# Sheet1_1.net
KiCad netlist of a schematic drawn in Altium Designer
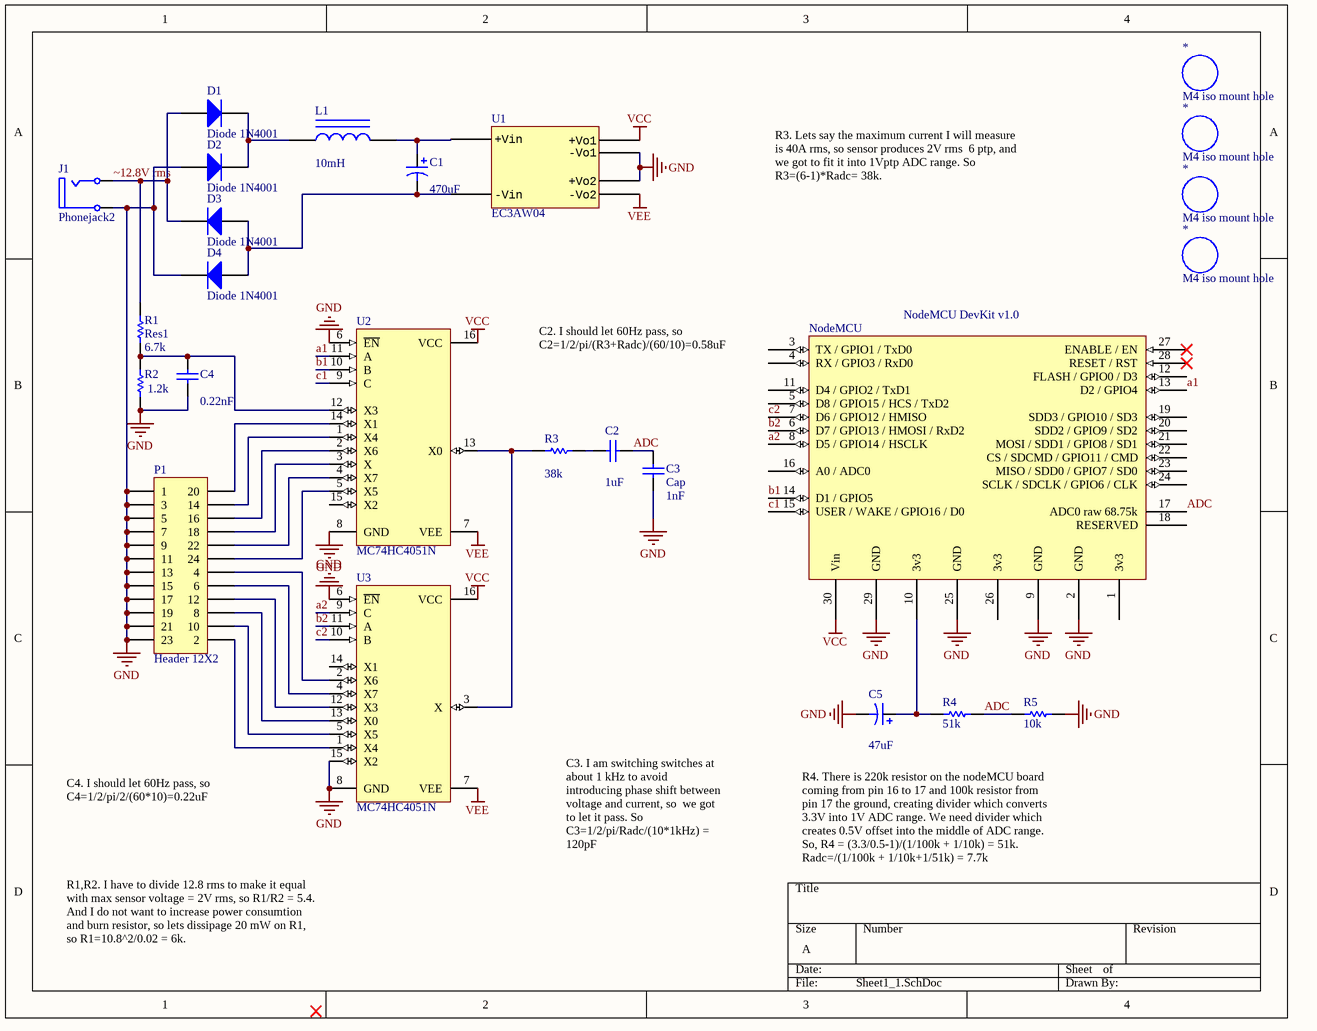
[diagram p0: Sheet1_1.SchDoc]

(export (version "E")
  (design (tool "Eeschema 10.0.6"))
  (components
    (comp (ref "C1")
      (value "470uF")
      (footprint "CAPPR5-12.5x25")
      (description "Polarized Capacitor (Radial)")
      (fields (field (name "Comment") "Cap Pol1") (field (name "PUBLISHER") "Altium Limited"))
      (libsource (lib "Miscellaneous Devices") (part "Cap Pol1"))
    )
    (comp (ref "C2")
      (value "1uF")
      (footprint "RAD-0.3")
      (description "Capacitor")
      (fields (field (name "Comment") "Cap") (field (name "PUBLISHER") "Altium Limited"))
      (libsource (lib "Miscellaneous Devices") (part "Cap"))
    )
    (comp (ref "C3")
      (value "Cap")
      (footprint "RAD-0.3")
      (description "Capacitor")
      (fields (field (name "ALTIUM_VALUE") "1nF") (field (name "PUBLISHER") "Altium Limited"))
      (libsource (lib "Miscellaneous Devices") (part "Cap"))
    )
    (comp (ref "C4")
      (value "0.22nF")
      (footprint "RAD-0.3")
      (description "Capacitor")
      (fields (field (name "Comment") "Cap") (field (name "PUBLISHER") "Altium Limited"))
      (libsource (lib "Miscellaneous Devices") (part "Cap"))
    )
    (comp (ref "C5")
      (value "47uF")
      (footprint "CAPPR2.5-6.3x6.8/H.9")
      (description "Polarized Capacitor (Radial)")
      (fields (field (name "Comment") "Cap Pol1") (field (name "PUBLISHER") "Altium Limited"))
      (libsource (lib "Miscellaneous Devices") (part "Cap Pol1"))
    )
    (comp (ref "D1")
      (value "Diode 1N4001")
      (footprint "DO-41")
      (description "1 Amp General Purpose Rectifier")
      (fields (field (name "PUBLISHER") "Altium Limited"))
      (libsource (lib "Miscellaneous Devices") (part "Diode 1N4001"))
    )
    (comp (ref "D2")
      (value "Diode 1N4001")
      (footprint "DO-41")
      (description "1 Amp General Purpose Rectifier")
      (fields (field (name "PUBLISHER") "Altium Limited"))
      (libsource (lib "Miscellaneous Devices") (part "Diode 1N4001"))
    )
    (comp (ref "D3")
      (value "Diode 1N4001")
      (footprint "DO-41")
      (description "1 Amp General Purpose Rectifier")
      (fields (field (name "PUBLISHER") "Altium Limited"))
      (libsource (lib "Miscellaneous Devices") (part "Diode 1N4001"))
    )
    (comp (ref "D4")
      (value "Diode 1N4001")
      (footprint "DO-41")
      (description "1 Amp General Purpose Rectifier")
      (fields (field (name "PUBLISHER") "Altium Limited"))
      (libsource (lib "Miscellaneous Devices") (part "Diode 1N4001"))
    )
    (comp (ref "J1")
      (value "Phonejack2")
      (footprint "Power jack 6x2mm")
      (description "Jack Socket, 1/4\" [6.5mm], Thru-Hole, Vertical, 2-Conductor Open Circuit")
      (fields (field (name "PUBLISHER") "Altium Limited"))
      (libsource (lib "AVP") (part "Phonejack2"))
    )
    (comp (ref "L1")
      (value "10mH")
      (footprint "Radial Vert Cylinder 10x19-6mm")
      (description "Magnetic-Core Inductor")
      (fields (field (name "Comment") "Inductor Iron") (field (name "PUBLISHER") "Altium Limited"))
      (libsource (lib "Miscellaneous Devices") (part "Inductor Iron"))
    )
    (comp (ref "NodeMCU")
      (value "NodeMCU DevKit v1.0")
      (footprint "NodeMCU DevKit v1.0 - Inside Labels")
      (libsource (lib "NodeMCU") (part "NodeMCU DevKit v1.0"))
    )
    (comp (ref "P1")
      (value "Header 12X2")
      (footprint "HDR2X12")
      (description "Header, 12-Pin, Dual row")
      (fields (field (name "PUBLISHER") "Altium Limited"))
      (libsource (lib "Miscellaneous Connectors") (part "Header 12X2"))
    )
    (comp (ref "R1")
      (value "Res1")
      (footprint "AXIAL-0.3")
      (description "Resistor")
      (fields (field (name "ALTIUM_VALUE") "6.7k") (field (name "PUBLISHER") "Altium Limited"))
      (libsource (lib "Miscellaneous Devices") (part "Res1"))
    )
    (comp (ref "R2")
      (value "1.2k")
      (footprint "AXIAL-0.3")
      (description "Resistor")
      (fields (field (name "Comment") "Res1") (field (name "PUBLISHER") "Altium Limited"))
      (libsource (lib "Miscellaneous Devices") (part "Res1"))
    )
    (comp (ref "R3")
      (value "38k")
      (footprint "AXIAL-0.3")
      (description "Resistor")
      (fields (field (name "Comment") "Res1") (field (name "PUBLISHER") "Altium Limited"))
      (libsource (lib "Miscellaneous Devices") (part "Res1"))
    )
    (comp (ref "R4")
      (value "51k")
      (footprint "AXIAL-0.3")
      (description "Resistor")
      (fields (field (name "Comment") "Res1") (field (name "PUBLISHER") "Altium Limited"))
      (libsource (lib "Miscellaneous Devices") (part "Res1"))
    )
    (comp (ref "R5")
      (value "10k")
      (footprint "AXIAL-0.3")
      (description "Resistor")
      (fields (field (name "Comment") "Res1") (field (name "PUBLISHER") "Altium Limited"))
      (libsource (lib "Miscellaneous Devices") (part "Res1"))
    )
    (comp (ref "U1") (value "EC3AW04") (footprint "EC3AW") (libsource (lib "AVP") (part "EC3AW04")))
    (comp (ref "U2")
      (value "MC74HC4051N")
      (footprint "648-08")
      (description "8-Channel Analog Multiplexer/Demultiplexer")
      (fields (field (name "PUBLISHER") "Altium Limited"))
      (libsource (lib "") (part "MC74HC4051N_1"))
    )
    (comp (ref "U3")
      (value "MC74HC4051N")
      (footprint "648-08")
      (description "8-Channel Analog Multiplexer/Demultiplexer")
      (fields (field (name "PUBLISHER") "Altium Limited"))
      (libsource (lib "ON Semi Logic Multiplexer") (part "MC74HC4051N"))
    )
  )
  (nets
    (net (code "1") (name "/ADC") (class "Default")
      (node (ref "C2") (pin "1") (pinfunction "1_1") (pintype "passive"))
      (node (ref "C3") (pin "2") (pinfunction "2_2") (pintype "passive"))
      (node (ref "NodeMCU") (pin "17") (pinfunction "ADC0_raw_68.75k_17") (pintype "passive"))
      (node (ref "R4") (pin "1") (pinfunction "1_1") (pintype "passive"))
      (node (ref "R5") (pin "2") (pinfunction "2_2") (pintype "passive"))
    )
    (net (code "2") (name "/a1") (class "Default")
      (node (ref "NodeMCU") (pin "13") (pinfunction "D2_/_GPIO4_13") (pintype "bidirectional"))
      (node (ref "U2") (pin "11") (pinfunction "A_11") (pintype "input"))
    )
    (net (code "3") (name "/a2") (class "Default")
      (node (ref "NodeMCU") (pin "8") (pinfunction "D5_/_GPIO14_/_HSCLK_8") (pintype "bidirectional"))
      (node (ref "U3") (pin "9") (pinfunction "C_9") (pintype "input"))
    )
    (net (code "4") (name "/b1") (class "Default")
      (node (ref "NodeMCU") (pin "14") (pinfunction "D1_/_GPIO5_14") (pintype "bidirectional"))
      (node (ref "U2") (pin "10") (pinfunction "B_10") (pintype "input"))
    )
    (net (code "5") (name "/b2") (class "Default")
      (node (ref "NodeMCU") (pin "6") (pinfunction "D7_/_GPIO13_/_HMOSI_/_RxD2_6") (pintype "bidirectional"))
      (node (ref "U3") (pin "11") (pinfunction "A_11") (pintype "input"))
    )
    (net (code "6") (name "/c1") (class "Default")
      (node (ref "NodeMCU") (pin "15") (pinfunction "USER_/_WAKE_/_GPIO16_/_D0_15") (pintype "bidirectional"))
      (node (ref "U2") (pin "9") (pinfunction "C_9") (pintype "input"))
    )
    (net (code "7") (name "/c2") (class "Default")
      (node (ref "NodeMCU") (pin "7") (pinfunction "D6_/_GPIO12_/_HMISO_7") (pintype "bidirectional"))
      (node (ref "U3") (pin "10") (pinfunction "B_10") (pintype "input"))
    )
    (net (code "8") (name "/~12.8V rms") (class "Default")
      (node (ref "D1") (pin "1") (pinfunction "A_1") (pintype "passive"))
      (node (ref "D3") (pin "2") (pinfunction "K_2") (pintype "passive"))
      (node (ref "J1") (pin "1") (pinfunction "T_1") (pintype "passive"))
      (node (ref "R1") (pin "2") (pinfunction "2_2") (pintype "passive"))
    )
    (net (code "9") (name "GND") (class "Default")
      (node (ref "C3") (pin "1") (pinfunction "1_1") (pintype "passive"))
      (node (ref "C4") (pin "1") (pinfunction "1_1") (pintype "passive"))
      (node (ref "C5") (pin "2") (pinfunction "2_2") (pintype "passive"))
      (node (ref "D2") (pin "1") (pinfunction "A_1") (pintype "passive"))
      (node (ref "D4") (pin "2") (pinfunction "K_2") (pintype "passive"))
      (node (ref "J1") (pin "5") (pinfunction "S_5") (pintype "power_in"))
      (node (ref "NodeMCU") (pin "2") (pinfunction "GND_2") (pintype "power_in"))
      (node (ref "NodeMCU") (pin "25") (pinfunction "GND_25") (pintype "power_in"))
      (node (ref "NodeMCU") (pin "29") (pinfunction "GND_29") (pintype "passive"))
      (node (ref "NodeMCU") (pin "9") (pinfunction "GND_9") (pintype "power_in"))
      (node (ref "P1") (pin "1") (pinfunction "1_1") (pintype "passive"))
      (node (ref "P1") (pin "11") (pinfunction "11_11") (pintype "passive"))
      (node (ref "P1") (pin "13") (pinfunction "13_13") (pintype "passive"))
      (node (ref "P1") (pin "15") (pinfunction "15_15") (pintype "passive"))
      (node (ref "P1") (pin "17") (pinfunction "17_17") (pintype "passive"))
      (node (ref "P1") (pin "19") (pinfunction "19_19") (pintype "passive"))
      (node (ref "P1") (pin "21") (pinfunction "21_21") (pintype "passive"))
      (node (ref "P1") (pin "23") (pinfunction "23_23") (pintype "passive"))
      (node (ref "P1") (pin "3") (pinfunction "3_3") (pintype "passive"))
      (node (ref "P1") (pin "5") (pinfunction "5_5") (pintype "passive"))
      (node (ref "P1") (pin "7") (pinfunction "7_7") (pintype "passive"))
      (node (ref "P1") (pin "9") (pinfunction "9_9") (pintype "passive"))
      (node (ref "R2") (pin "2") (pinfunction "2_2") (pintype "passive"))
      (node (ref "R5") (pin "1") (pinfunction "1_1") (pintype "passive"))
      (node (ref "U1") (pin "10") (pinfunction "-Vo1_10") (pintype "power_in"))
      (node (ref "U1") (pin "3") (pinfunction "+Vo2_3") (pintype "power_in"))
      (node (ref "U2") (pin "6") (pinfunction "~{EN}_6") (pintype "input"))
      (node (ref "U2") (pin "8") (pinfunction "GND_8") (pintype "power_in"))
      (node (ref "U3") (pin "15") (pinfunction "X2_15") (pintype "bidirectional"))
      (node (ref "U3") (pin "6") (pinfunction "~{EN}_6") (pintype "input"))
      (node (ref "U3") (pin "8") (pinfunction "GND_8") (pintype "power_in"))
    )
    (net (code "10") (name "Net-(C2-Pad2)") (class "Default")
      (node (ref "C2") (pin "2") (pinfunction "2_2") (pintype "passive"))
      (node (ref "R3") (pin "2") (pinfunction "2_2") (pintype "passive"))
    )
    (net (code "11") (name "Net-(C5-Pad1)") (class "Default")
      (node (ref "C5") (pin "1") (pinfunction "1_1") (pintype "passive"))
      (node (ref "NodeMCU") (pin "10") (pinfunction "3v3_10") (pintype "power_in"))
      (node (ref "R4") (pin "2") (pinfunction "2_2") (pintype "passive"))
    )
    (net (code "12") (name "Net-(D1-K)") (class "Default")
      (node (ref "D1") (pin "2") (pinfunction "K_2") (pintype "passive"))
      (node (ref "D2") (pin "2") (pinfunction "K_2") (pintype "passive"))
      (node (ref "L1") (pin "1") (pinfunction "1_1") (pintype "passive"))
    )
    (net (code "13") (name "Net-(D3-A)") (class "Default")
      (node (ref "C1") (pin "2") (pinfunction "2_2") (pintype "passive"))
      (node (ref "D3") (pin "1") (pinfunction "A_1") (pintype "passive"))
      (node (ref "D4") (pin "1") (pinfunction "A_1") (pintype "passive"))
      (node (ref "U1") (pin "12") (pinfunction "-Vin_12") (pintype "power_in"))
    )
    (net (code "14") (name "Net-(U1-+Vin)") (class "Default")
      (node (ref "C1") (pin "1") (pinfunction "1_1") (pintype "passive"))
      (node (ref "L1") (pin "2") (pinfunction "2_2") (pintype "passive"))
      (node (ref "U1") (pin "1") (pinfunction "+Vin_1") (pintype "power_in"))
    )
    (net (code "15") (name "Net-(U2-X)") (class "Default")
      (node (ref "P1") (pin "18") (pinfunction "18_18") (pintype "passive"))
      (node (ref "U2") (pin "3") (pinfunction "X_3") (pintype "bidirectional"))
    )
    (net (code "16") (name "Net-(U2-X0)") (class "Default")
      (node (ref "R3") (pin "1") (pinfunction "1_1") (pintype "passive"))
      (node (ref "U2") (pin "13") (pinfunction "X0_13") (pintype "bidirectional"))
      (node (ref "U3") (pin "3") (pinfunction "X_3") (pintype "bidirectional"))
    )
    (net (code "17") (name "Net-(U2-X1)") (class "Default")
      (node (ref "P1") (pin "20") (pinfunction "20_20") (pintype "passive"))
      (node (ref "U2") (pin "14") (pinfunction "X1_14") (pintype "bidirectional"))
    )
    (net (code "18") (name "Net-(U2-X3)") (class "Default")
      (node (ref "C4") (pin "2") (pinfunction "2_2") (pintype "passive"))
      (node (ref "R1") (pin "1") (pinfunction "1_1") (pintype "passive"))
      (node (ref "R2") (pin "1") (pinfunction "1_1") (pintype "passive"))
      (node (ref "U2") (pin "12") (pinfunction "X3_12") (pintype "bidirectional"))
    )
    (net (code "19") (name "Net-(U2-X4)") (class "Default")
      (node (ref "P1") (pin "14") (pinfunction "14_14") (pintype "passive"))
      (node (ref "U2") (pin "1") (pinfunction "X4_1") (pintype "bidirectional"))
    )
    (net (code "20") (name "Net-(U2-X5)") (class "Default")
      (node (ref "P1") (pin "24") (pinfunction "24_24") (pintype "passive"))
      (node (ref "U2") (pin "5") (pinfunction "X5_5") (pintype "bidirectional"))
    )
    (net (code "21") (name "Net-(U2-X6)") (class "Default")
      (node (ref "P1") (pin "16") (pinfunction "16_16") (pintype "passive"))
      (node (ref "U2") (pin "2") (pinfunction "X6_2") (pintype "bidirectional"))
    )
    (net (code "22") (name "Net-(U2-X7)") (class "Default")
      (node (ref "P1") (pin "22") (pinfunction "22_22") (pintype "passive"))
      (node (ref "U2") (pin "4") (pinfunction "X7_4") (pintype "bidirectional"))
    )
    (net (code "23") (name "Net-(U3-X0)") (class "Default")
      (node (ref "P1") (pin "8") (pinfunction "8_8") (pintype "passive"))
      (node (ref "U3") (pin "13") (pinfunction "X0_13") (pintype "bidirectional"))
    )
    (net (code "24") (name "Net-(U3-X3)") (class "Default")
      (node (ref "P1") (pin "12") (pinfunction "12_12") (pintype "passive"))
      (node (ref "U3") (pin "12") (pinfunction "X3_12") (pintype "bidirectional"))
    )
    (net (code "25") (name "Net-(U3-X4)") (class "Default")
      (node (ref "P1") (pin "2") (pinfunction "2_2") (pintype "passive"))
      (node (ref "U3") (pin "1") (pinfunction "X4_1") (pintype "bidirectional"))
    )
    (net (code "26") (name "Net-(U3-X5)") (class "Default")
      (node (ref "P1") (pin "10") (pinfunction "10_10") (pintype "passive"))
      (node (ref "U3") (pin "5") (pinfunction "X5_5") (pintype "bidirectional"))
    )
    (net (code "27") (name "Net-(U3-X6)") (class "Default")
      (node (ref "P1") (pin "4") (pinfunction "4_4") (pintype "passive"))
      (node (ref "U3") (pin "2") (pinfunction "X6_2") (pintype "bidirectional"))
    )
    (net (code "28") (name "Net-(U3-X7)") (class "Default")
      (node (ref "P1") (pin "6") (pinfunction "6_6") (pintype "passive"))
      (node (ref "U3") (pin "4") (pinfunction "X7_4") (pintype "bidirectional"))
    )
    (net (code "29") (name "VCC") (class "Default")
      (node (ref "NodeMCU") (pin "30") (pinfunction "Vin_30") (pintype "passive"))
      (node (ref "U1") (pin "11") (pinfunction "+Vo1_11") (pintype "power_in"))
      (node (ref "U2") (pin "16") (pinfunction "VCC_16") (pintype "power_in"))
      (node (ref "U3") (pin "16") (pinfunction "VCC_16") (pintype "power_in"))
    )
    (net (code "30") (name "VEE") (class "Default")
      (node (ref "U1") (pin "2") (pinfunction "-Vo2_2") (pintype "power_in"))
      (node (ref "U2") (pin "7") (pinfunction "VEE_7") (pintype "power_in"))
      (node (ref "U3") (pin "7") (pinfunction "VEE_7") (pintype "power_in"))
    )
    (net (code "31") (name "unconnected-(NodeMCU-3v3-Pad1)") (class "Default")
      (node (ref "NodeMCU") (pin "1") (pinfunction "3v3_1") (pintype "power_in"))
    )
    (net (code "32") (name "unconnected-(NodeMCU-3v3-Pad26)") (class "Default")
      (node (ref "NodeMCU") (pin "26") (pinfunction "3v3_26") (pintype "power_in"))
    )
    (net (code "33") (name "unconnected-(NodeMCU-A0_{slash}_ADC0-Pad16)") (class "Default")
      (node (ref "NodeMCU") (pin "16") (pinfunction "A0_/_ADC0_16") (pintype "bidirectional"))
    )
    (net (code "34") (name "unconnected-(NodeMCU-CS_{slash}_SDCMD_{slash}_GPIO11_{slash}_CMD-Pad22)") (class "Default")
      (node (ref "NodeMCU") (pin "22") (pinfunction "CS_/_SDCMD_/_GPIO11_/_CMD_22") (pintype "bidirectional"))
    )
    (net (code "35") (name "unconnected-(NodeMCU-D4_{slash}_GPIO2_{slash}_TxD1-Pad11)") (class "Default")
      (node (ref "NodeMCU") (pin "11") (pinfunction "D4_/_GPIO2_/_TxD1_11") (pintype "bidirectional"))
    )
    (net (code "36") (name "unconnected-(NodeMCU-D8_{slash}_GPIO15_{slash}_HCS_{slash}_TxD2-Pad5)") (class "Default")
      (node (ref "NodeMCU") (pin "5") (pinfunction "D8_/_GPIO15_/_HCS_/_TxD2_5") (pintype "bidirectional"))
    )
    (net (code "37") (name "unconnected-(NodeMCU-ENABLE_{slash}_EN-Pad27)") (class "Default")
      (node (ref "NodeMCU") (pin "27") (pinfunction "ENABLE_/_EN_27") (pintype "input+no_connect"))
    )
    (net (code "38") (name "unconnected-(NodeMCU-FLASH_{slash}_GPIO0_{slash}_D3-Pad12)") (class "Default")
      (node (ref "NodeMCU") (pin "12") (pinfunction "FLASH_/_GPIO0_/_D3_12") (pintype "bidirectional"))
    )
    (net (code "39") (name "unconnected-(NodeMCU-MISO_{slash}_SDD0_{slash}_GPIO7_{slash}_SD0-Pad23)") (class "Default")
      (node (ref "NodeMCU") (pin "23") (pinfunction "MISO_/_SDD0_/_GPIO7_/_SD0_23") (pintype "bidirectional"))
    )
    (net (code "40") (name "unconnected-(NodeMCU-MOSI_{slash}_SDD1_{slash}_GPIO8_{slash}_SD1-Pad21)") (class "Default")
      (node (ref "NodeMCU") (pin "21") (pinfunction "MOSI_/_SDD1_/_GPIO8_/_SD1_21") (pintype "bidirectional"))
    )
    (net (code "41") (name "unconnected-(NodeMCU-RESERVED-Pad18)") (class "Default")
      (node (ref "NodeMCU") (pin "18") (pinfunction "RESERVED_18") (pintype "passive"))
    )
    (net (code "42") (name "unconnected-(NodeMCU-RESET_{slash}_RST-Pad28)") (class "Default")
      (node (ref "NodeMCU") (pin "28") (pinfunction "RESET_/_RST_28") (pintype "input+no_connect"))
    )
    (net (code "43") (name "unconnected-(NodeMCU-RX_{slash}_GPIO3_{slash}_RxD0-Pad4)") (class "Default")
      (node (ref "NodeMCU") (pin "4") (pinfunction "RX_/_GPIO3_/_RxD0_4") (pintype "bidirectional"))
    )
    (net (code "44") (name "unconnected-(NodeMCU-SCLK_{slash}_SDCLK_{slash}_GPIO6_{slash}_CLK-Pad24)") (class "Default")
      (node (ref "NodeMCU") (pin "24") (pinfunction "SCLK_/_SDCLK_/_GPIO6_/_CLK_24") (pintype "bidirectional"))
    )
    (net (code "45") (name "unconnected-(NodeMCU-SDD2_{slash}_GPIO9_{slash}_SD2-Pad20)") (class "Default")
      (node (ref "NodeMCU") (pin "20") (pinfunction "SDD2_/_GPIO9_/_SD2_20") (pintype "bidirectional"))
    )
    (net (code "46") (name "unconnected-(NodeMCU-SDD3_{slash}_GPIO10_{slash}_SD3-Pad19)") (class "Default")
      (node (ref "NodeMCU") (pin "19") (pinfunction "SDD3_/_GPIO10_/_SD3_19") (pintype "bidirectional"))
    )
    (net (code "47") (name "unconnected-(NodeMCU-TX_{slash}_GPIO1_{slash}_TxD0-Pad3)") (class "Default")
      (node (ref "NodeMCU") (pin "3") (pinfunction "TX_/_GPIO1_/_TxD0_3") (pintype "bidirectional"))
    )
    (net (code "48") (name "unconnected-(U2-X2-Pad15)") (class "Default")
      (node (ref "U2") (pin "15") (pinfunction "X2_15") (pintype "bidirectional"))
    )
    (net (code "49") (name "unconnected-(U3-X1-Pad14)") (class "Default")
      (node (ref "U3") (pin "14") (pinfunction "X1_14") (pintype "bidirectional"))
    )
  )
)
